# SbusServoTray.net
KiCad netlist of a schematic drawn in Altium Designer
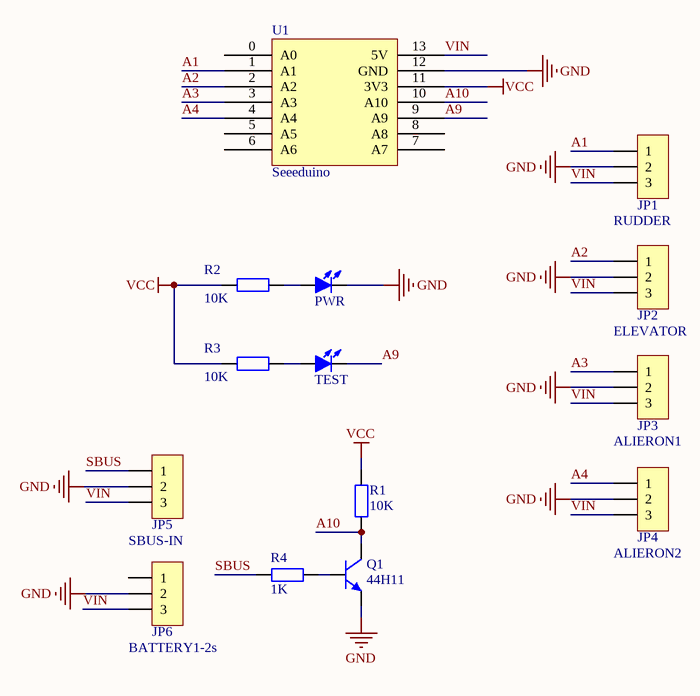
[diagram p0: SbusServoTray.SchDoc]

(export (version "E")
  (design (tool "Eeschema 10.0.6"))
  (components
    (comp (ref "JP1")
      (value "RUDDER")
      (footprint "2.54-3P")
      (description "3P接插件")
      (fields (field (name "版权归属") "源创客"))
      (libsource (lib "SbusServoTray") (part "Header 3"))
    )
    (comp (ref "JP2")
      (value "ELEVATOR")
      (footprint "2.54-3P")
      (description "3P接插件")
      (fields (field (name "版权归属") "源创客"))
      (libsource (lib "SbusServoTray") (part "Header 3"))
    )
    (comp (ref "JP3")
      (value "ALIERON1")
      (footprint "2.54-3P")
      (description "3P接插件")
      (fields (field (name "版权归属") "源创客"))
      (libsource (lib "SbusServoTray") (part "Header 3"))
    )
    (comp (ref "JP4")
      (value "ALIERON2")
      (footprint "2.54-3P")
      (description "3P接插件")
      (fields (field (name "版权归属") "源创客"))
      (libsource (lib "SbusServoTray") (part "Header 3"))
    )
    (comp (ref "JP5")
      (value "SBUS-IN")
      (footprint "HDR2.54-WI-3P")
      (description "3P接插件")
      (fields (field (name "版权归属") "源创客"))
      (libsource (lib "SbusServoTray") (part "Header 3"))
    )
    (comp (ref "JP6")
      (value "BATTERY1-2s")
      (footprint "HDR2.54-WI-3P")
      (description "3P接插件")
      (fields (field (name "版权归属") "源创客"))
      (libsource (lib "SbusServoTray") (part "Header 3"))
    )
    (comp (ref "PWR")
      (value "红色")
      (footprint "LED 0805B")
      (description "贴片LED")
      (fields (field (name "版权归属") "源创客"))
      (libsource (lib "SbusServoTray") (part "LED-SMD"))
    )
    (comp (ref "Q1")
      (value "44H11")
      (footprint "SOT23-3N")
      (description "互补功率-NPN型")
      (fields (field (name "版权归属") "源创客"))
      (libsource (lib "SbusServoTray") (part "44H11"))
    )
    (comp (ref "R1")
      (value "10K")
      (footprint "0805R")
      (description "贴片电阻")
      (fields (field (name "版权归属") "源创客"))
      (libsource (lib "SbusServoTray") (part "R"))
    )
    (comp (ref "R2")
      (value "10K")
      (footprint "0805R")
      (description "贴片电阻")
      (fields (field (name "版权归属") "源创客"))
      (libsource (lib "SbusServoTray") (part "R"))
    )
    (comp (ref "R3")
      (value "10K")
      (footprint "0805R")
      (description "贴片电阻")
      (fields (field (name "版权归属") "源创客"))
      (libsource (lib "SbusServoTray") (part "R"))
    )
    (comp (ref "R4")
      (value "1K")
      (footprint "0805R")
      (description "贴片电阻")
      (fields (field (name "版权归属") "源创客"))
      (libsource (lib "SbusServoTray") (part "R"))
    )
    (comp (ref "TEST")
      (value "红色")
      (footprint "LED 0805W")
      (description "贴片LED")
      (fields (field (name "版权归属") "源创客"))
      (libsource (lib "SbusServoTray") (part "LED-SMD"))
    )
    (comp (ref "U1")
      (value "Seeeduino")
      (footprint "Seeeduino")
      (libsource (lib "SbusServoTray") (part "Seeeduino"))
    )
  )
  (nets
    (net (code "1") (name "/A1") (class "Default")
      (node (ref "JP1") (pin "1") (pinfunction "1_1") (pintype "passive"))
      (node (ref "U1") (pin "1") (pinfunction "A1_1") (pintype "passive"))
    )
    (net (code "2") (name "/A2") (class "Default")
      (node (ref "JP2") (pin "1") (pinfunction "1_1") (pintype "passive"))
      (node (ref "U1") (pin "2") (pinfunction "A2_2") (pintype "passive"))
    )
    (net (code "3") (name "/A3") (class "Default")
      (node (ref "JP3") (pin "1") (pinfunction "1_1") (pintype "passive"))
      (node (ref "U1") (pin "3") (pinfunction "A3_3") (pintype "passive"))
    )
    (net (code "4") (name "/A4") (class "Default")
      (node (ref "JP4") (pin "1") (pinfunction "1_1") (pintype "passive"))
      (node (ref "U1") (pin "4") (pinfunction "A4_4") (pintype "passive"))
    )
    (net (code "5") (name "/A9") (class "Default")
      (node (ref "TEST") (pin "2") (pinfunction "K_2") (pintype "passive"))
      (node (ref "U1") (pin "9") (pinfunction "A9_9") (pintype "passive"))
    )
    (net (code "6") (name "/A10") (class "Default")
      (node (ref "Q1") (pin "2") (pinfunction "C_2") (pintype "passive"))
      (node (ref "R1") (pin "2") (pinfunction "2_2") (pintype "passive"))
      (node (ref "U1") (pin "10") (pinfunction "A10_10") (pintype "passive"))
    )
    (net (code "7") (name "/SBUS") (class "Default")
      (node (ref "JP5") (pin "1") (pinfunction "1_1") (pintype "passive"))
      (node (ref "R4") (pin "1") (pinfunction "1_1") (pintype "passive"))
    )
    (net (code "8") (name "/VIN") (class "Default")
      (node (ref "JP1") (pin "3") (pinfunction "3_3") (pintype "passive"))
      (node (ref "JP2") (pin "3") (pinfunction "3_3") (pintype "passive"))
      (node (ref "JP3") (pin "3") (pinfunction "3_3") (pintype "passive"))
      (node (ref "JP4") (pin "3") (pinfunction "3_3") (pintype "passive"))
      (node (ref "JP5") (pin "3") (pinfunction "3_3") (pintype "passive"))
      (node (ref "JP6") (pin "3") (pinfunction "3_3") (pintype "passive"))
      (node (ref "U1") (pin "13") (pinfunction "5V_13") (pintype "passive"))
    )
    (net (code "9") (name "GND") (class "Default")
      (node (ref "JP1") (pin "2") (pinfunction "2_2") (pintype "passive"))
      (node (ref "JP2") (pin "2") (pinfunction "2_2") (pintype "passive"))
      (node (ref "JP3") (pin "2") (pinfunction "2_2") (pintype "passive"))
      (node (ref "JP4") (pin "2") (pinfunction "2_2") (pintype "passive"))
      (node (ref "JP5") (pin "2") (pinfunction "2_2") (pintype "passive"))
      (node (ref "JP6") (pin "2") (pinfunction "2_2") (pintype "passive"))
      (node (ref "PWR") (pin "2") (pinfunction "K_2") (pintype "passive"))
      (node (ref "Q1") (pin "3") (pinfunction "E_3") (pintype "passive"))
      (node (ref "U1") (pin "12") (pinfunction "GND_12") (pintype "passive"))
    )
    (net (code "10") (name "Net-(PWR-A)") (class "Default")
      (node (ref "PWR") (pin "1") (pinfunction "A_1") (pintype "passive"))
      (node (ref "R2") (pin "2") (pinfunction "2_2") (pintype "passive"))
    )
    (net (code "11") (name "Net-(Q1-B)") (class "Default")
      (node (ref "Q1") (pin "1") (pinfunction "B_1") (pintype "passive"))
      (node (ref "R4") (pin "2") (pinfunction "2_2") (pintype "passive"))
    )
    (net (code "12") (name "Net-(TEST-A)") (class "Default")
      (node (ref "R3") (pin "2") (pinfunction "2_2") (pintype "passive"))
      (node (ref "TEST") (pin "1") (pinfunction "A_1") (pintype "passive"))
    )
    (net (code "13") (name "VCC") (class "Default")
      (node (ref "R1") (pin "1") (pinfunction "1_1") (pintype "passive"))
      (node (ref "R2") (pin "1") (pinfunction "1_1") (pintype "passive"))
      (node (ref "R3") (pin "1") (pinfunction "1_1") (pintype "passive"))
      (node (ref "U1") (pin "11") (pinfunction "3V3_11") (pintype "passive"))
    )
    (net (code "14") (name "unconnected-(JP6-Pad1)") (class "Default")
      (node (ref "JP6") (pin "1") (pinfunction "1_1") (pintype "passive"))
    )
    (net (code "15") (name "unconnected-(U1-A0-Pad0)") (class "Default")
      (node (ref "U1") (pin "0") (pinfunction "A0_0") (pintype "passive"))
    )
    (net (code "16") (name "unconnected-(U1-A5-Pad5)") (class "Default")
      (node (ref "U1") (pin "5") (pinfunction "A5_5") (pintype "passive"))
    )
    (net (code "17") (name "unconnected-(U1-A6-Pad6)") (class "Default")
      (node (ref "U1") (pin "6") (pinfunction "A6_6") (pintype "passive"))
    )
    (net (code "18") (name "unconnected-(U1-A7-Pad7)") (class "Default")
      (node (ref "U1") (pin "7") (pinfunction "A7_7") (pintype "passive"))
    )
    (net (code "19") (name "unconnected-(U1-A8-Pad8)") (class "Default")
      (node (ref "U1") (pin "8") (pinfunction "A8_8") (pintype "passive"))
    )
  )
)
